# SY_HR08_MCU_INTERFACE_V1_1.net
KiCad netlist of a schematic drawn in Altium Designer
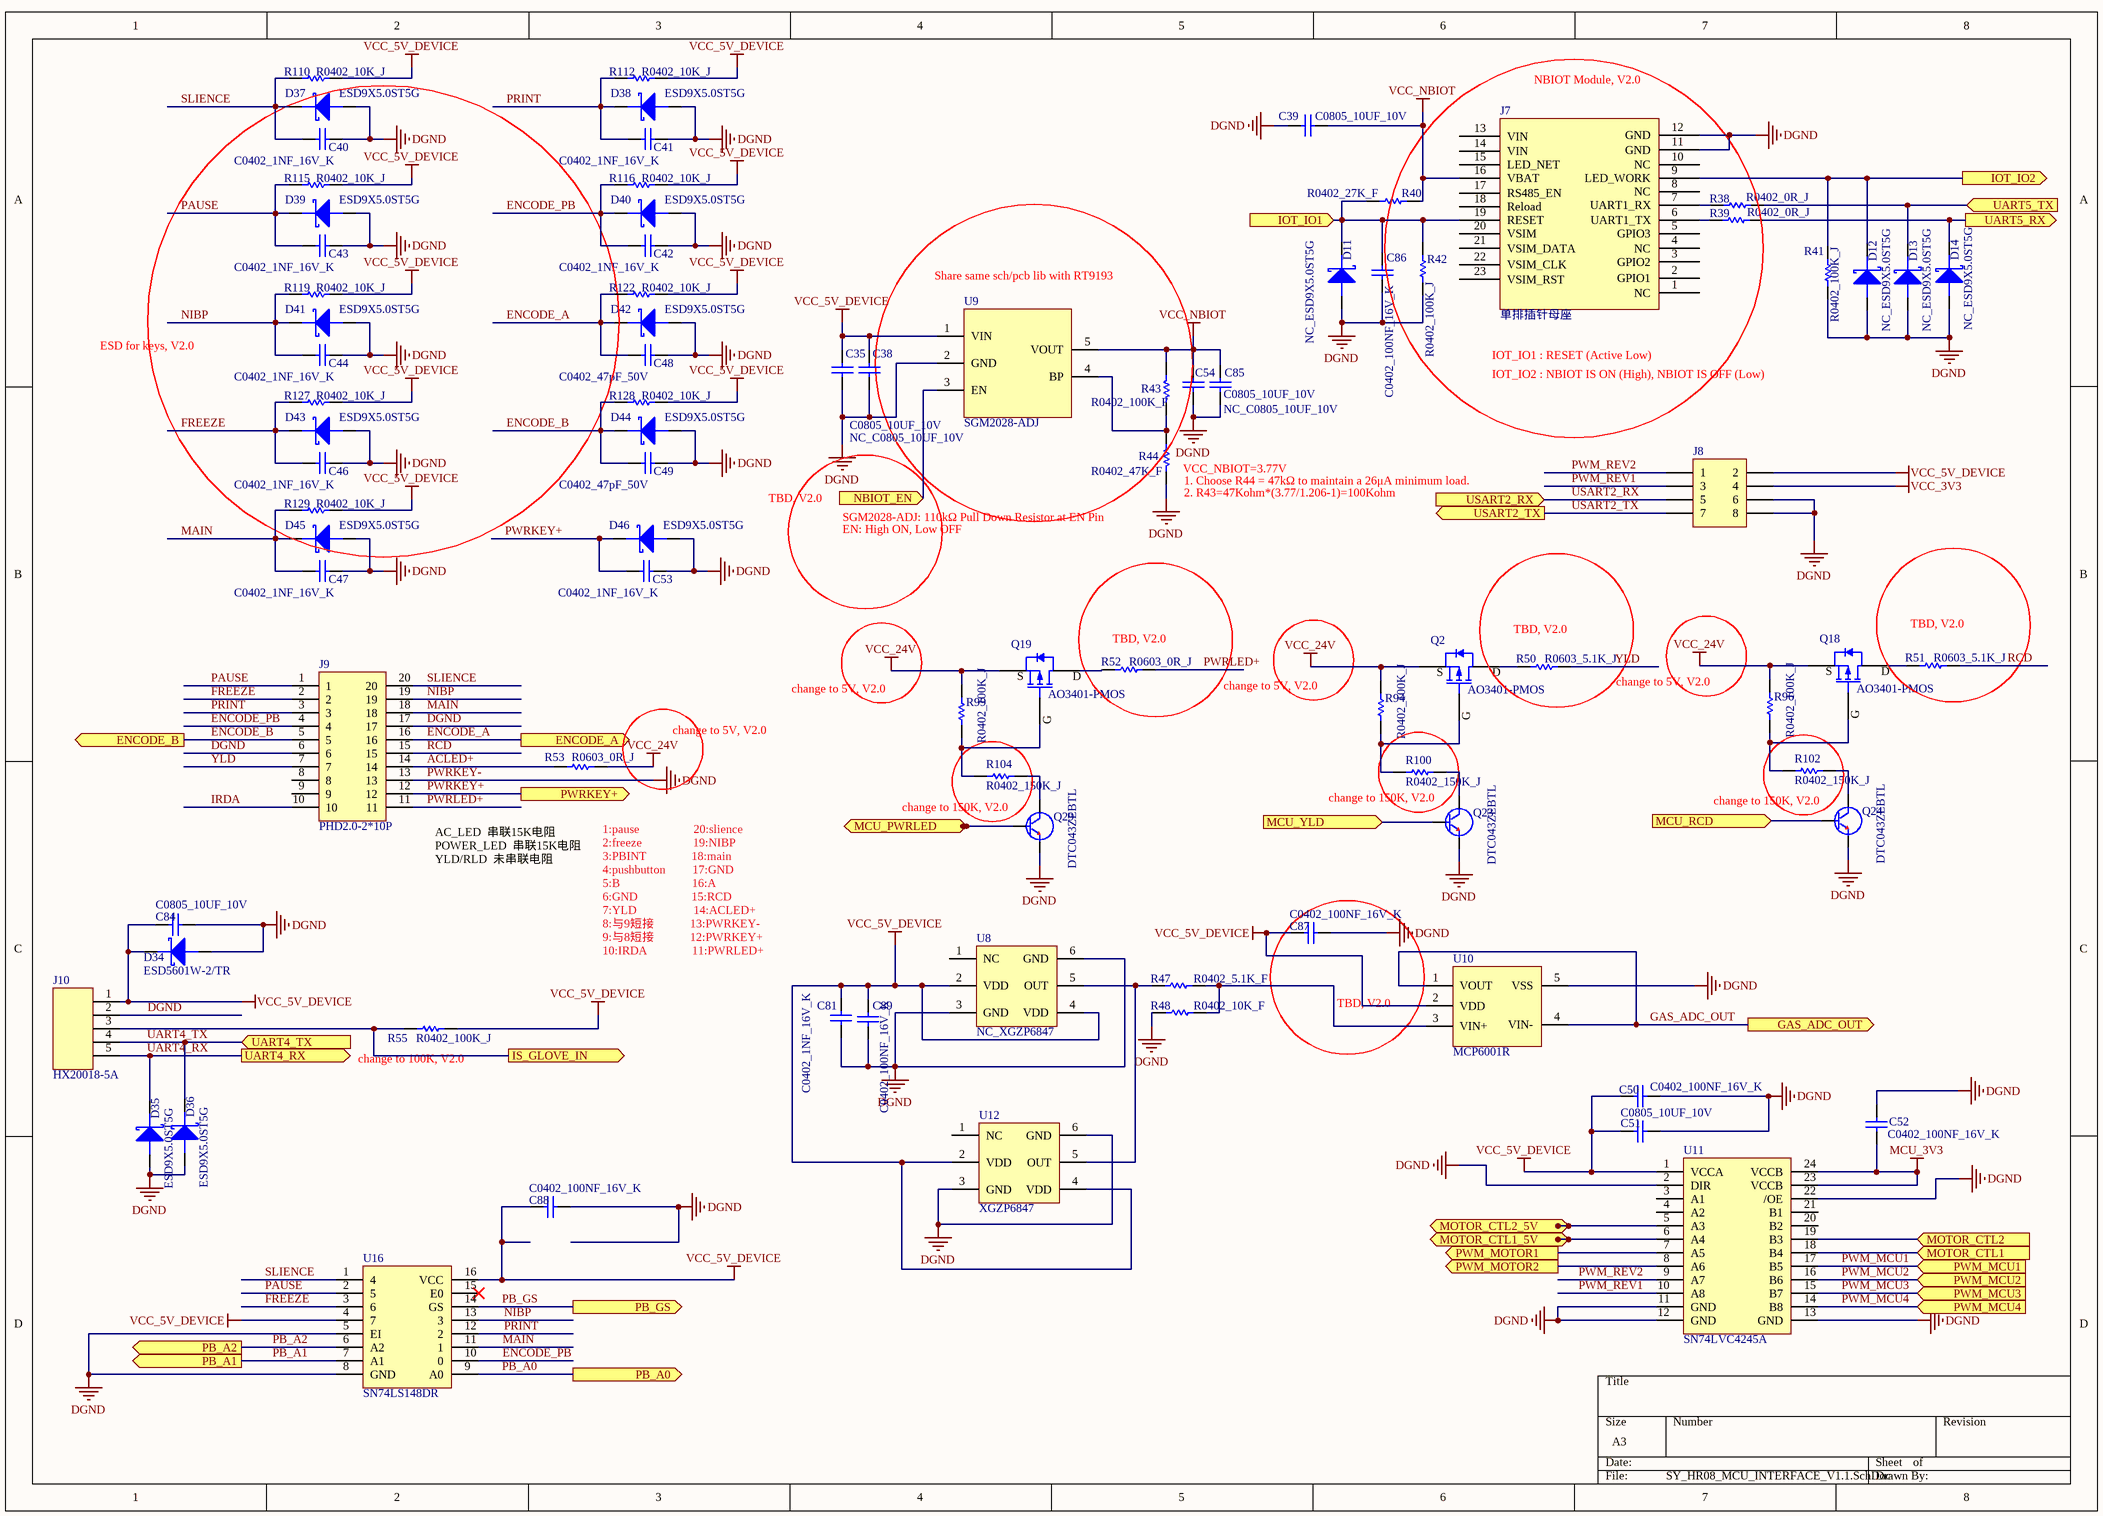
[diagram p0: SY_HR08_MCU_INTERFACE_V1.1.SchDoc]

(export (version "E")
  (design (tool "Eeschema 10.0.6"))
  (components
    (comp (ref "C35")
      (value "C0805_10UF_10V")
      (footprint "CAP0805-B")
      (description "电容_10uF_0805_X5R_10V_K")
      (libsource (lib "zhangky_sch") (part "C0805_10UF_10V"))
    )
    (comp (ref "C38")
      (value "NC_C0805_10UF_10V")
      (footprint "CAP0805-B")
      (description "电容_10uF_0805_X5R_10V_K")
      (libsource (lib "zhangky_sch") (part "C0805_10UF_10V"))
    )
    (comp (ref "C39")
      (value "C0805_10UF_10V")
      (footprint "CAP0805-B")
      (description "电容_10uF_0805_X5R_10V_K")
      (libsource (lib "zhangky_sch") (part "C0805_10UF_10V"))
    )
    (comp (ref "C40")
      (value "C0402_1NF_16V_K")
      (footprint "CAP0402_HQ")
      (description "电容_100nF_0402_X7R_16V_K")
      (libsource (lib "zhangky_sch") (part "C0402_100NF_16V_K"))
    )
    (comp (ref "C41")
      (value "C0402_1NF_16V_K")
      (footprint "CAP0402_HQ")
      (description "电容_100nF_0402_X7R_16V_K")
      (libsource (lib "zhangky_sch") (part "C0402_100NF_16V_K"))
    )
    (comp (ref "C42")
      (value "C0402_1NF_16V_K")
      (footprint "CAP0402_HQ")
      (description "电容_100nF_0402_X7R_16V_K")
      (libsource (lib "zhangky_sch") (part "C0402_100NF_16V_K"))
    )
    (comp (ref "C43")
      (value "C0402_1NF_16V_K")
      (footprint "CAP0402_HQ")
      (description "电容_100nF_0402_X7R_16V_K")
      (libsource (lib "zhangky_sch") (part "C0402_100NF_16V_K"))
    )
    (comp (ref "C44")
      (value "C0402_1NF_16V_K")
      (footprint "CAP0402_HQ")
      (description "电容_100nF_0402_X7R_16V_K")
      (libsource (lib "zhangky_sch") (part "C0402_100NF_16V_K"))
    )
    (comp (ref "C46")
      (value "C0402_1NF_16V_K")
      (footprint "CAP0402_HQ")
      (description "电容_100nF_0402_X7R_16V_K")
      (libsource (lib "zhangky_sch") (part "C0402_100NF_16V_K"))
    )
    (comp (ref "C47")
      (value "C0402_1NF_16V_K")
      (footprint "CAP0402_HQ")
      (description "电容_100nF_0402_X7R_16V_K")
      (libsource (lib "zhangky_sch") (part "C0402_100NF_16V_K"))
    )
    (comp (ref "C48")
      (value "C0402_47pF_50V")
      (footprint "CAP0402_HQ")
      (description "电容_100nF_0402_X7R_16V_K")
      (libsource (lib "zhangky_sch") (part "C0402_100NF_16V_K"))
    )
    (comp (ref "C49")
      (value "C0402_47pF_50V")
      (footprint "CAP0402_HQ")
      (description "电容_100nF_0402_X7R_16V_K")
      (libsource (lib "zhangky_sch") (part "C0402_100NF_16V_K"))
    )
    (comp (ref "C50")
      (value "C0402_100NF_16V_K")
      (footprint "CAP0402_HQ")
      (description "电容_100nF_0402_X7R_16V_K")
      (libsource (lib "zhangky_sch") (part "C0402_100NF_16V_K"))
    )
    (comp (ref "C51")
      (value "C0805_10UF_10V")
      (footprint "CAP0805-B")
      (description "电容_10uF_0805_X5R_10V_K")
      (libsource (lib "zhangky_sch") (part "C0805_10UF_10V"))
    )
    (comp (ref "C52")
      (value "C0402_100NF_16V_K")
      (footprint "CAP0402_HQ")
      (description "电容_100nF_0402_X7R_16V_K")
      (libsource (lib "zhangky_sch") (part "C0402_100NF_16V_K"))
    )
    (comp (ref "C53")
      (value "C0402_1NF_16V_K")
      (footprint "CAP0402_HQ")
      (description "电容_100nF_0402_X7R_16V_K")
      (libsource (lib "zhangky_sch") (part "C0402_100NF_16V_K"))
    )
    (comp (ref "C54")
      (value "NC_C0805_10UF_10V")
      (footprint "CAP0805-B")
      (description "电容_10uF_0805_X5R_10V_K")
      (libsource (lib "zhangky_sch") (part "C0805_10UF_10V"))
    )
    (comp (ref "C81")
      (value "C0402_1NF_16V_K")
      (footprint "CAP0402_HQ")
      (description "电容_100nF_0402_X7R_16V_K")
      (libsource (lib "zhangky_sch") (part "C0402_100NF_16V_K"))
    )
    (comp (ref "C84")
      (value "C0805_10UF_10V")
      (footprint "CAP0805-B")
      (description "电容_10uF_0805_X5R_10V_K")
      (libsource (lib "zhangky_sch") (part "C0805_10UF_10V"))
    )
    (comp (ref "C85")
      (value "C0805_10UF_10V")
      (footprint "CAP0805-B")
      (description "电容_10uF_0805_X5R_10V_K")
      (libsource (lib "zhangky_sch") (part "C0805_10UF_10V"))
    )
    (comp (ref "C86")
      (value "C0402_100NF_16V_K")
      (footprint "CAP0402_HQ")
      (description "电容_100nF_0402_X7R_16V_K")
      (libsource (lib "zhangky_sch") (part "C0402_100NF_16V_K"))
    )
    (comp (ref "C87")
      (value "C0402_100NF_16V_K")
      (footprint "CAP0402_HQ")
      (description "电容_100nF_0402_X7R_16V_K")
      (libsource (lib "zhangky_sch") (part "C0402_100NF_16V_K"))
    )
    (comp (ref "C88")
      (value "C0402_100NF_16V_K")
      (footprint "CAP0402_HQ")
      (description "电容_100nF_0402_X7R_16V_K")
      (libsource (lib "zhangky_sch") (part "C0402_100NF_16V_K"))
    )
    (comp (ref "C89")
      (value "C0402_100NF_16V_K")
      (footprint "CAP0402_HQ")
      (description "电容_100nF_0402_X7R_16V_K")
      (libsource (lib "zhangky_sch") (part "C0402_100NF_16V_K"))
    )
    (comp (ref "D11")
      (value "NC_ESD9X5.0ST5G")
      (footprint "ESD9X5.0ST5G")
      (description "TVS_单路_单向_5.0V_65pF")
      (fields (field (name "MANUFACTURER") "ONSEMI(安森美)") (field (name "PART NUMBER") "HQ11510010010"))
      (libsource (lib "zhangky_sch") (part "ESD9X5.0ST5G"))
    )
    (comp (ref "D12")
      (value "NC_ESD9X5.0ST5G")
      (footprint "ESD9X5.0ST5G")
      (description "TVS_单路_单向_5.0V_65pF")
      (fields (field (name "MANUFACTURER") "ONSEMI(安森美)") (field (name "PART NUMBER") "HQ11510010010"))
      (libsource (lib "zhangky_sch") (part "ESD9X5.0ST5G"))
    )
    (comp (ref "D13")
      (value "NC_ESD9X5.0ST5G")
      (footprint "ESD9X5.0ST5G")
      (description "TVS_单路_单向_5.0V_65pF")
      (fields (field (name "MANUFACTURER") "ONSEMI(安森美)") (field (name "PART NUMBER") "HQ11510010010"))
      (libsource (lib "zhangky_sch") (part "ESD9X5.0ST5G"))
    )
    (comp (ref "D14")
      (value "NC_ESD9X5.0ST5G")
      (footprint "ESD9X5.0ST5G")
      (description "TVS_单路_单向_5.0V_65pF")
      (fields (field (name "MANUFACTURER") "ONSEMI(安森美)") (field (name "PART NUMBER") "HQ11510010010"))
      (libsource (lib "zhangky_sch") (part "ESD9X5.0ST5G"))
    )
    (comp (ref "D34")
      (value "ESD5601W-2/TR")
      (footprint "ESD5601W-2$2F$TR")
      (description "TVS_浪涌+静电二合一管_单向_7V_170pf")
      (fields (field (name "MANUFACTURER") "Will(韦尔)") (field (name "PART NUMBER") "HQ11510029000"))
      (libsource (lib "zhangky_sch") (part "ESD5601W-2/TR"))
    )
    (comp (ref "D35")
      (value "ESD9X5.0ST5G")
      (footprint "ESD9X5.0ST5G")
      (description "TVS_单路_单向_5.0V_65pF")
      (fields (field (name "MANUFACTURER") "ONSEMI(安森美)") (field (name "PART NUMBER") "HQ11510010010"))
      (libsource (lib "zhangky_sch") (part "ESD9X5.0ST5G"))
    )
    (comp (ref "D36")
      (value "ESD9X5.0ST5G")
      (footprint "ESD9X5.0ST5G")
      (description "TVS_单路_单向_5.0V_65pF")
      (fields (field (name "MANUFACTURER") "ONSEMI(安森美)") (field (name "PART NUMBER") "HQ11510010010"))
      (libsource (lib "zhangky_sch") (part "ESD9X5.0ST5G"))
    )
    (comp (ref "D37")
      (value "ESD9X5.0ST5G")
      (footprint "ESD9X5.0ST5G")
      (description "TVS_单路_单向_5.0V_65pF")
      (fields (field (name "MANUFACTURER") "ONSEMI(安森美)") (field (name "PART NUMBER") "HQ11510010010"))
      (libsource (lib "zhangky_sch") (part "ESD9X5.0ST5G"))
    )
    (comp (ref "D38")
      (value "ESD9X5.0ST5G")
      (footprint "ESD9X5.0ST5G")
      (description "TVS_单路_单向_5.0V_65pF")
      (fields (field (name "MANUFACTURER") "ONSEMI(安森美)") (field (name "PART NUMBER") "HQ11510010010"))
      (libsource (lib "zhangky_sch") (part "ESD9X5.0ST5G"))
    )
    (comp (ref "D39")
      (value "ESD9X5.0ST5G")
      (footprint "ESD9X5.0ST5G")
      (description "TVS_单路_单向_5.0V_65pF")
      (fields (field (name "MANUFACTURER") "ONSEMI(安森美)") (field (name "PART NUMBER") "HQ11510010010"))
      (libsource (lib "zhangky_sch") (part "ESD9X5.0ST5G"))
    )
    (comp (ref "D40")
      (value "ESD9X5.0ST5G")
      (footprint "ESD9X5.0ST5G")
      (description "TVS_单路_单向_5.0V_65pF")
      (fields (field (name "MANUFACTURER") "ONSEMI(安森美)") (field (name "PART NUMBER") "HQ11510010010"))
      (libsource (lib "zhangky_sch") (part "ESD9X5.0ST5G"))
    )
    (comp (ref "D41")
      (value "ESD9X5.0ST5G")
      (footprint "ESD9X5.0ST5G")
      (description "TVS_单路_单向_5.0V_65pF")
      (fields (field (name "MANUFACTURER") "ONSEMI(安森美)") (field (name "PART NUMBER") "HQ11510010010"))
      (libsource (lib "zhangky_sch") (part "ESD9X5.0ST5G"))
    )
    (comp (ref "D42")
      (value "ESD9X5.0ST5G")
      (footprint "ESD9X5.0ST5G")
      (description "TVS_单路_单向_5.0V_65pF")
      (fields (field (name "MANUFACTURER") "ONSEMI(安森美)") (field (name "PART NUMBER") "HQ11510010010"))
      (libsource (lib "zhangky_sch") (part "ESD9X5.0ST5G"))
    )
    (comp (ref "D43")
      (value "ESD9X5.0ST5G")
      (footprint "ESD9X5.0ST5G")
      (description "TVS_单路_单向_5.0V_65pF")
      (fields (field (name "MANUFACTURER") "ONSEMI(安森美)") (field (name "PART NUMBER") "HQ11510010010"))
      (libsource (lib "zhangky_sch") (part "ESD9X5.0ST5G"))
    )
    (comp (ref "D44")
      (value "ESD9X5.0ST5G")
      (footprint "ESD9X5.0ST5G")
      (description "TVS_单路_单向_5.0V_65pF")
      (fields (field (name "MANUFACTURER") "ONSEMI(安森美)") (field (name "PART NUMBER") "HQ11510010010"))
      (libsource (lib "zhangky_sch") (part "ESD9X5.0ST5G"))
    )
    (comp (ref "D45")
      (value "ESD9X5.0ST5G")
      (footprint "ESD9X5.0ST5G")
      (description "TVS_单路_单向_5.0V_65pF")
      (fields (field (name "MANUFACTURER") "ONSEMI(安森美)") (field (name "PART NUMBER") "HQ11510010010"))
      (libsource (lib "zhangky_sch") (part "ESD9X5.0ST5G"))
    )
    (comp (ref "D46")
      (value "ESD9X5.0ST5G")
      (footprint "ESD9X5.0ST5G")
      (description "TVS_单路_单向_5.0V_65pF")
      (fields (field (name "MANUFACTURER") "ONSEMI(安森美)") (field (name "PART NUMBER") "HQ11510010010"))
      (libsource (lib "zhangky_sch") (part "ESD9X5.0ST5G"))
    )
    (comp (ref "J7")
      (value "单排插针母座")
      (footprint "USR-LTE-7S4")
      (libsource (lib "USR-NB75 V1.0.1") (part "USR-NB75"))
    )
    (comp (ref "J8")
      (value "双排插针")
      (footprint "CON2X4(2.54MM)")
      (description "Header, 4-Pin, Dual row")
      (libsource (lib "zhangky_sch") (part "Header 4X2"))
    )
    (comp (ref "J9")
      (value "PHD2.0-2*10P")
      (footprint "PHD2.0-20P")
      (description "2.0mm间距接插件 双排插座")
      (libsource (lib "zhangky_sch") (part "PHD2.0-20P"))
    )
    (comp (ref "J10")
      (value "HX20018-5A")
      (footprint "HX20018-5A")
      (description "HX20018-5A  2.0mm")
      (libsource (lib "zhangky_sch") (part "HX20018-5A"))
    )
    (comp (ref "Q2")
      (value "AO3401-PMOS")
      (footprint "AO3400")
      (libsource (lib "zhangky_sch") (part "AO3401-PMOS"))
    )
    (comp (ref "Q18")
      (value "AO3401-PMOS")
      (footprint "AO3400")
      (libsource (lib "zhangky_sch") (part "AO3401-PMOS"))
    )
    (comp (ref "Q19")
      (value "AO3401-PMOS")
      (footprint "AO3400")
      (libsource (lib "zhangky_sch") (part "AO3401-PMOS"))
    )
    (comp (ref "Q23")
      (value "DTC043ZEBTL")
      (footprint "DTC043ZEBTL$2F$$2F$DTC143ZE$2F$$2F$LDTC143ZET1G")
      (description "NPN三极管_100mA_EMT3F")
      (libsource (lib "zhangky_sch") (part "DTC043ZEBTL"))
    )
    (comp (ref "Q24")
      (value "DTC043ZEBTL")
      (footprint "DTC043ZEBTL$2F$$2F$DTC143ZE$2F$$2F$LDTC143ZET1G")
      (description "NPN三极管_100mA_EMT3F")
      (libsource (lib "zhangky_sch") (part "DTC043ZEBTL"))
    )
    (comp (ref "Q29")
      (value "DTC043ZEBTL")
      (footprint "DTC043ZEBTL$2F$$2F$DTC143ZE$2F$$2F$LDTC143ZET1G")
      (description "NPN三极管_100mA_EMT3F")
      (libsource (lib "zhangky_sch") (part "DTC043ZEBTL"))
    )
    (comp (ref "R38")
      (value "R0402_0R_J")
      (footprint "RES0402_HQ")
      (description "电阻10K(0402-0.0625W-J)")
      (libsource (lib "zhangky_sch") (part "R0402_10K_J"))
    )
    (comp (ref "R39")
      (value "R0402_0R_J")
      (footprint "RES0402_HQ")
      (description "电阻10K(0402-0.0625W-J)")
      (libsource (lib "zhangky_sch") (part "R0402_10K_J"))
    )
    (comp (ref "R40")
      (value "R0402_27K_F")
      (footprint "RES0402_HQ")
      (description "电阻10K(0402-0.0625W-J)")
      (libsource (lib "zhangky_sch") (part "R0402_10K_J"))
    )
    (comp (ref "R41")
      (value "R0402_100K_J")
      (footprint "RES0402_HQ")
      (description "电阻10K(0402-0.0625W-J)")
      (libsource (lib "zhangky_sch") (part "R0402_10K_J"))
    )
    (comp (ref "R42")
      (value "R0402_100K_J")
      (footprint "RES0402_HQ")
      (description "电阻10K(0402-0.0625W-J)")
      (libsource (lib "zhangky_sch") (part "R0402_10K_J"))
    )
    (comp (ref "R43")
      (value "R0402_100K_F")
      (footprint "RES0402_HQ")
      (description "电阻10K(0402-0.0625W-J)")
      (libsource (lib "zhangky_sch") (part "R0402_10K_J"))
    )
    (comp (ref "R44")
      (value "R0402_47K_F")
      (footprint "RES0402_HQ")
      (description "电阻10K(0402-0.0625W-J)")
      (libsource (lib "zhangky_sch") (part "R0402_10K_J"))
    )
    (comp (ref "R47")
      (value "R0402_5.1K_F")
      (footprint "RES0402_HQ")
      (description "电阻100K(0402-0.0625W-J)")
      (libsource (lib "zhangky_sch") (part "R0402_100K_J"))
    )
    (comp (ref "R48")
      (value "R0402_10K_F")
      (footprint "RES0402_HQ")
      (description "电阻100K(0402-0.0625W-J)")
      (libsource (lib "zhangky_sch") (part "R0402_100K_J"))
    )
    (comp (ref "R50")
      (value "R0603_5.1K_J")
      (footprint "RES0603-A")
      (description "电阻0R(0603-0.1W-J)")
      (libsource (lib "zhangky_sch") (part "R0603_0R_J"))
    )
    (comp (ref "R51")
      (value "R0603_5.1K_J")
      (footprint "RES0603-A")
      (description "电阻0R(0603-0.1W-J)")
      (libsource (lib "zhangky_sch") (part "R0603_0R_J"))
    )
    (comp (ref "R52")
      (value "R0603_0R_J")
      (footprint "RES0603-A")
      (description "电阻0R(0603-0.1W-J)")
      (libsource (lib "zhangky_sch") (part "R0603_0R_J"))
    )
    (comp (ref "R53")
      (value "R0603_0R_J")
      (footprint "RES0603-A")
      (description "电阻0R(0603-0.1W-J)")
      (libsource (lib "zhangky_sch") (part "R0603_0R_J"))
    )
    (comp (ref "R55")
      (value "R0402_100K_J")
      (footprint "RES0402_HQ")
      (description "电阻10K(0402-0.0625W-J)")
      (libsource (lib "zhangky_sch") (part "R0402_10K_J"))
    )
    (comp (ref "R94")
      (value "R0402_100K_J")
      (footprint "RES0402_HQ")
      (description "电阻100K(0402-0.0625W-J)")
      (libsource (lib "zhangky_sch") (part "R0402_100K_J"))
    )
    (comp (ref "R96")
      (value "R0402_100K_J")
      (footprint "RES0402_HQ")
      (description "电阻100K(0402-0.0625W-J)")
      (libsource (lib "zhangky_sch") (part "R0402_100K_J"))
    )
    (comp (ref "R99")
      (value "R0402_100K_J")
      (footprint "RES0402_HQ")
      (description "电阻100K(0402-0.0625W-J)")
      (libsource (lib "zhangky_sch") (part "R0402_100K_J"))
    )
    (comp (ref "R100")
      (value "R0402_150K_J")
      (footprint "RES0402_HQ")
      (description "电阻100K(0402-0.0625W-J)")
      (libsource (lib "zhangky_sch") (part "R0402_100K_J"))
    )
    (comp (ref "R102")
      (value "R0402_150K_J")
      (footprint "RES0402_HQ")
      (description "电阻100K(0402-0.0625W-J)")
      (libsource (lib "zhangky_sch") (part "R0402_100K_J"))
    )
    (comp (ref "R104")
      (value "R0402_150K_J")
      (footprint "RES0402_HQ")
      (description "电阻100K(0402-0.0625W-J)")
      (libsource (lib "zhangky_sch") (part "R0402_100K_J"))
    )
    (comp (ref "R110")
      (value "R0402_10K_J")
      (footprint "RES0402_HQ")
      (description "电阻10K(0402-0.0625W-J)")
      (libsource (lib "zhangky_sch") (part "R0402_10K_J"))
    )
    (comp (ref "R112")
      (value "R0402_10K_J")
      (footprint "RES0402_HQ")
      (description "电阻10K(0402-0.0625W-J)")
      (libsource (lib "zhangky_sch") (part "R0402_10K_J"))
    )
    (comp (ref "R115")
      (value "R0402_10K_J")
      (footprint "RES0402_HQ")
      (description "电阻10K(0402-0.0625W-J)")
      (libsource (lib "zhangky_sch") (part "R0402_10K_J"))
    )
    (comp (ref "R116")
      (value "R0402_10K_J")
      (footprint "RES0402_HQ")
      (description "电阻10K(0402-0.0625W-J)")
      (libsource (lib "zhangky_sch") (part "R0402_10K_J"))
    )
    (comp (ref "R119")
      (value "R0402_10K_J")
      (footprint "RES0402_HQ")
      (description "电阻10K(0402-0.0625W-J)")
      (libsource (lib "zhangky_sch") (part "R0402_10K_J"))
    )
    (comp (ref "R122")
      (value "R0402_10K_J")
      (footprint "RES0402_HQ")
      (description "电阻10K(0402-0.0625W-J)")
      (libsource (lib "zhangky_sch") (part "R0402_10K_J"))
    )
    (comp (ref "R127")
      (value "R0402_10K_J")
      (footprint "RES0402_HQ")
      (description "电阻10K(0402-0.0625W-J)")
      (libsource (lib "zhangky_sch") (part "R0402_10K_J"))
    )
    (comp (ref "R128")
      (value "R0402_10K_J")
      (footprint "RES0402_HQ")
      (description "电阻10K(0402-0.0625W-J)")
      (libsource (lib "zhangky_sch") (part "R0402_10K_J"))
    )
    (comp (ref "R129")
      (value "R0402_10K_J")
      (footprint "RES0402_HQ")
      (description "电阻10K(0402-0.0625W-J)")
      (libsource (lib "zhangky_sch") (part "R0402_10K_J"))
    )
    (comp (ref "U8")
      (value "NC_XGZP6847")
      (footprint "XGZP6847300KPA")
      (description "XGZP6847_300KPG  气压范围-100kpa - 300kpa")
      (libsource (lib "zhangky_sch") (part "XGZP6847"))
    )
    (comp (ref "U9")
      (value "SGM2028-ADJ")
      (footprint "TPS7B6950")
      (description "单电池电压转换器  3.3V")
      (libsource (lib "zhangky_sch") (part "RT9193-33"))
    )
    (comp (ref "U10")
      (value "MCP6001R")
      (footprint "TOS23")
      (description "1MHz, Low-Power Op Amp")
      (libsource (lib "zhangky_sch") (part "MCP6001R"))
    )
    (comp (ref "U11")
      (value "SN74LVC4245A")
      (footprint "SN74LVC4245APW")
      (description "3.3V 至 5V 移位器")
      (libsource (lib "zhangky_sch") (part "SN74LVC4245AWP"))
    )
    (comp (ref "U12")
      (value "XGZP6847")
      (footprint "XGZP6847300KPA")
      (description "XGZP6847_300KPG  气压范围-100kpa - 300kpa")
      (libsource (lib "zhangky_sch") (part "XGZP6847"))
    )
    (comp (ref "U16")
      (value "SN74LS148DR")
      (footprint "SOIC16_39MM")
      (description "8 线路到 3 线路优先编码器")
      (libsource (lib "zhangky_sch") (part "SN74LS148DR"))
    )
  )
  (nets
    (net (code "1") (name "/ACLED+") (class "Default")
      (node (ref "J9") (pin "14") (pinfunction "14_14") (pintype "passive"))
      (node (ref "R53") (pin "1") (pinfunction "1_1") (pintype "passive"))
    )
    (net (code "2") (name "/ENCODE_A") (class "Default")
      (node (ref "C48") (pin "2") (pinfunction "2_2") (pintype "passive"))
      (node (ref "D42") (pin "1") (pinfunction "1_1") (pintype "passive"))
      (node (ref "J9") (pin "16") (pinfunction "16_16") (pintype "passive"))
      (node (ref "R122") (pin "1") (pinfunction "1_1") (pintype "passive"))
    )
    (net (code "3") (name "/ENCODE_B") (class "Default")
      (node (ref "C49") (pin "2") (pinfunction "2_2") (pintype "passive"))
      (node (ref "D44") (pin "1") (pinfunction "1_1") (pintype "passive"))
      (node (ref "J9") (pin "5") (pinfunction "5_5") (pintype "passive"))
      (node (ref "R128") (pin "1") (pinfunction "1_1") (pintype "passive"))
    )
    (net (code "4") (name "/ENCODE_PB") (class "Default")
      (node (ref "C42") (pin "2") (pinfunction "2_2") (pintype "passive"))
      (node (ref "D40") (pin "1") (pinfunction "1_1") (pintype "passive"))
      (node (ref "J9") (pin "4") (pinfunction "4_4") (pintype "passive"))
      (node (ref "R116") (pin "1") (pinfunction "1_1") (pintype "passive"))
      (node (ref "U16") (pin "10") (pinfunction "0_10") (pintype "passive"))
    )
    (net (code "5") (name "/FREEZE") (class "Default")
      (node (ref "C46") (pin "2") (pinfunction "2_2") (pintype "passive"))
      (node (ref "D43") (pin "1") (pinfunction "1_1") (pintype "passive"))
      (node (ref "J9") (pin "2") (pinfunction "2_2") (pintype "passive"))
      (node (ref "R127") (pin "1") (pinfunction "1_1") (pintype "passive"))
      (node (ref "U16") (pin "3") (pinfunction "6_3") (pintype "passive"))
    )
    (net (code "6") (name "/GAS_ADC_OUT") (class "Default")
      (node (ref "U10") (pin "1") (pinfunction "VOUT_1") (pintype "passive"))
      (node (ref "U10") (pin "4") (pinfunction "VIN-_4") (pintype "passive"))
    )
    (net (code "7") (name "/IOT_IO1") (class "Default")
      (node (ref "C86") (pin "1") (pinfunction "1_1") (pintype "passive"))
      (node (ref "D11") (pin "1") (pinfunction "1_1") (pintype "passive"))
      (node (ref "J7") (pin "19") (pinfunction "RESET_19") (pintype "passive"))
      (node (ref "R40") (pin "2") (pinfunction "2_2") (pintype "passive"))
      (node (ref "R42") (pin "1") (pinfunction "1_1") (pintype "passive"))
    )
    (net (code "8") (name "/IOT_IO2") (class "Default")
      (node (ref "D12") (pin "1") (pinfunction "1_1") (pintype "passive"))
      (node (ref "J7") (pin "9") (pinfunction "LED_WORK_9") (pintype "passive"))
      (node (ref "R41") (pin "2") (pinfunction "2_2") (pintype "passive"))
    )
    (net (code "9") (name "/IRDA") (class "Default")
      (node (ref "J9") (pin "10") (pinfunction "10_10") (pintype "passive"))
    )
    (net (code "10") (name "/IS_GLOVE_IN") (class "Default")
      (node (ref "J10") (pin "3") (pinfunction "3_3") (pintype "passive"))
      (node (ref "R55") (pin "1") (pinfunction "1_1") (pintype "passive"))
    )
    (net (code "11") (name "/MAIN") (class "Default")
      (node (ref "C47") (pin "2") (pinfunction "2_2") (pintype "passive"))
      (node (ref "D45") (pin "1") (pinfunction "1_1") (pintype "passive"))
      (node (ref "J9") (pin "18") (pinfunction "18_18") (pintype "passive"))
      (node (ref "R129") (pin "1") (pinfunction "1_1") (pintype "passive"))
      (node (ref "U16") (pin "11") (pinfunction "1_11") (pintype "passive"))
    )
    (net (code "12") (name "/MCU_PWRLED") (class "Default")
      (node (ref "Q29") (pin "1") (pinfunction "B_1") (pintype "passive"))
    )
    (net (code "13") (name "/MCU_RCD") (class "Default")
      (node (ref "Q24") (pin "1") (pinfunction "B_1") (pintype "passive"))
    )
    (net (code "14") (name "/MCU_YLD") (class "Default")
      (node (ref "Q23") (pin "1") (pinfunction "B_1") (pintype "passive"))
    )
    (net (code "15") (name "/MOTOR_CTL1") (class "Default")
      (node (ref "U11") (pin "18") (pinfunction "B4_18") (pintype "passive"))
    )
    (net (code "16") (name "/MOTOR_CTL1_5V") (class "Default")
      (node (ref "U11") (pin "6") (pinfunction "A4_6") (pintype "passive"))
    )
    (net (code "17") (name "/MOTOR_CTL2") (class "Default")
      (node (ref "U11") (pin "19") (pinfunction "B3_19") (pintype "passive"))
    )
    (net (code "18") (name "/MOTOR_CTL2_5V") (class "Default")
      (node (ref "U11") (pin "5") (pinfunction "A3_5") (pintype "passive"))
    )
    (net (code "19") (name "/NBIOT_EN") (class "Default")
      (node (ref "U9") (pin "3") (pinfunction "EN_3") (pintype "passive"))
    )
    (net (code "20") (name "/NIBP") (class "Default")
      (node (ref "C44") (pin "2") (pinfunction "2_2") (pintype "passive"))
      (node (ref "D41") (pin "1") (pinfunction "1_1") (pintype "passive"))
      (node (ref "J9") (pin "19") (pinfunction "19_19") (pintype "passive"))
      (node (ref "R119") (pin "1") (pinfunction "1_1") (pintype "passive"))
      (node (ref "U16") (pin "13") (pinfunction "3_13") (pintype "passive"))
    )
    (net (code "21") (name "/PAUSE") (class "Default")
      (node (ref "C43") (pin "2") (pinfunction "2_2") (pintype "passive"))
      (node (ref "D39") (pin "1") (pinfunction "1_1") (pintype "passive"))
      (node (ref "J9") (pin "1") (pinfunction "1_1") (pintype "passive"))
      (node (ref "R115") (pin "1") (pinfunction "1_1") (pintype "passive"))
      (node (ref "U16") (pin "2") (pinfunction "5_2") (pintype "passive"))
    )
    (net (code "22") (name "/PB_A0") (class "Default")
      (node (ref "U16") (pin "9") (pinfunction "A0_9") (pintype "passive"))
    )
    (net (code "23") (name "/PB_A1") (class "Default")
      (node (ref "U16") (pin "7") (pinfunction "A1_7") (pintype "passive"))
    )
    (net (code "24") (name "/PB_A2") (class "Default")
      (node (ref "U16") (pin "6") (pinfunction "A2_6") (pintype "passive"))
    )
    (net (code "25") (name "/PB_GS") (class "Default")
      (node (ref "U16") (pin "14") (pinfunction "GS_14") (pintype "passive"))
    )
    (net (code "26") (name "/PRINT") (class "Default")
      (node (ref "C41") (pin "2") (pinfunction "2_2") (pintype "passive"))
      (node (ref "D38") (pin "1") (pinfunction "1_1") (pintype "passive"))
      (node (ref "J9") (pin "3") (pinfunction "3_3") (pintype "passive"))
      (node (ref "R112") (pin "1") (pinfunction "1_1") (pintype "passive"))
      (node (ref "U16") (pin "12") (pinfunction "2_12") (pintype "passive"))
    )
    (net (code "27") (name "/PWM_MCU1") (class "Default")
      (node (ref "U11") (pin "17") (pinfunction "B5_17") (pintype "passive"))
    )
    (net (code "28") (name "/PWM_MCU2") (class "Default")
      (node (ref "U11") (pin "16") (pinfunction "B6_16") (pintype "passive"))
    )
    (net (code "29") (name "/PWM_MCU3") (class "Default")
      (node (ref "U11") (pin "15") (pinfunction "B7_15") (pintype "passive"))
    )
    (net (code "30") (name "/PWM_MCU4") (class "Default")
      (node (ref "U11") (pin "14") (pinfunction "B8_14") (pintype "passive"))
    )
    (net (code "31") (name "/PWM_MOTOR1") (class "Default")
      (node (ref "U11") (pin "7") (pinfunction "A5_7") (pintype "passive"))
    )
    (net (code "32") (name "/PWM_MOTOR2") (class "Default")
      (node (ref "U11") (pin "8") (pinfunction "A6_8") (pintype "passive"))
    )
    (net (code "33") (name "/PWM_REV1") (class "Default")
      (node (ref "J8") (pin "3") (pinfunction "3_3") (pintype "passive"))
      (node (ref "U11") (pin "10") (pinfunction "A8_10") (pintype "passive"))
    )
    (net (code "34") (name "/PWM_REV2") (class "Default")
      (node (ref "J8") (pin "1") (pinfunction "1_1") (pintype "passive"))
      (node (ref "U11") (pin "9") (pinfunction "A7_9") (pintype "passive"))
    )
    (net (code "35") (name "/PWRKEY+") (class "Default")
      (node (ref "C53") (pin "2") (pinfunction "2_2") (pintype "passive"))
      (node (ref "D46") (pin "1") (pinfunction "1_1") (pintype "passive"))
      (node (ref "J9") (pin "12") (pinfunction "12_12") (pintype "passive"))
    )
    (net (code "36") (name "/PWRLED+") (class "Default")
      (node (ref "J9") (pin "11") (pinfunction "11_11") (pintype "passive"))
      (node (ref "R52") (pin "2") (pinfunction "2_2") (pintype "passive"))
    )
    (net (code "37") (name "/RCD") (class "Default")
      (node (ref "J9") (pin "15") (pinfunction "15_15") (pintype "passive"))
      (node (ref "R51") (pin "2") (pinfunction "2_2") (pintype "passive"))
    )
    (net (code "38") (name "/SLIENCE") (class "Default")
      (node (ref "C40") (pin "2") (pinfunction "2_2") (pintype "passive"))
      (node (ref "D37") (pin "1") (pinfunction "1_1") (pintype "passive"))
      (node (ref "J9") (pin "20") (pinfunction "20_20") (pintype "passive"))
      (node (ref "R110") (pin "1") (pinfunction "1_1") (pintype "passive"))
      (node (ref "U16") (pin "1") (pinfunction "4_1") (pintype "passive"))
    )
    (net (code "39") (name "/UART4_RX") (class "Default")
      (node (ref "D35") (pin "1") (pinfunction "1_1") (pintype "passive"))
      (node (ref "J10") (pin "5") (pinfunction "5_5") (pintype "passive"))
    )
    (net (code "40") (name "/UART4_TX") (class "Default")
      (node (ref "D36") (pin "1") (pinfunction "1_1") (pintype "passive"))
      (node (ref "J10") (pin "4") (pinfunction "4_4") (pintype "passive"))
    )
    (net (code "41") (name "/UART5_RX") (class "Default")
      (node (ref "D14") (pin "1") (pinfunction "1_1") (pintype "passive"))
      (node (ref "R39") (pin "1") (pinfunction "1_1") (pintype "passive"))
    )
    (net (code "42") (name "/UART5_TX") (class "Default")
      (node (ref "D13") (pin "1") (pinfunction "1_1") (pintype "passive"))
      (node (ref "R38") (pin "2") (pinfunction "2_2") (pintype "passive"))
    )
    (net (code "43") (name "/USART2_RX") (class "Default")
      (node (ref "J8") (pin "5") (pinfunction "5_5") (pintype "passive"))
    )
    (net (code "44") (name "/USART2_TX") (class "Default")
      (node (ref "J8") (pin "7") (pinfunction "7_7") (pintype "passive"))
    )
    (net (code "45") (name "/YLD") (class "Default")
      (node (ref "J9") (pin "7") (pinfunction "7_7") (pintype "passive"))
      (node (ref "R50") (pin "2") (pinfunction "2_2") (pintype "passive"))
    )
    (net (code "46") (name "DGND") (class "Default")
      (node (ref "C35") (pin "1") (pinfunction "1_1") (pintype "passive"))
      (node (ref "C38") (pin "1") (pinfunction "1_1") (pintype "passive"))
      (node (ref "C39") (pin "2") (pinfunction "2_2") (pintype "passive"))
      (node (ref "C40") (pin "1") (pinfunction "1_1") (pintype "passive"))
      (node (ref "C41") (pin "1") (pinfunction "1_1") (pintype "passive"))
      (node (ref "C42") (pin "1") (pinfunction "1_1") (pintype "passive"))
      (node (ref "C43") (pin "1") (pinfunction "1_1") (pintype "passive"))
      (node (ref "C44") (pin "1") (pinfunction "1_1") (pintype "passive"))
      (node (ref "C46") (pin "1") (pinfunction "1_1") (pintype "passive"))
      (node (ref "C47") (pin "1") (pinfunction "1_1") (pintype "passive"))
      (node (ref "C48") (pin "1") (pinfunction "1_1") (pintype "passive"))
      (node (ref "C49") (pin "1") (pinfunction "1_1") (pintype "passive"))
      (node (ref "C50") (pin "1") (pinfunction "1_1") (pintype "passive"))
      (node (ref "C51") (pin "2") (pinfunction "2_2") (pintype "passive"))
      (node (ref "C52") (pin "1") (pinfunction "1_1") (pintype "passive"))
      (node (ref "C53") (pin "1") (pinfunction "1_1") (pintype "passive"))
      (node (ref "C54") (pin "1") (pinfunction "1_1") (pintype "passive"))
      (node (ref "C81") (pin "2") (pinfunction "2_2") (pintype "passive"))
      (node (ref "C84") (pin "2") (pinfunction "2_2") (pintype "passive"))
      (node (ref "C85") (pin "1") (pinfunction "1_1") (pintype "passive"))
      (node (ref "C86") (pin "2") (pinfunction "2_2") (pintype "passive"))
      (node (ref "C87") (pin "1") (pinfunction "1_1") (pintype "passive"))
      (node (ref "C88") (pin "1") (pinfunction "1_1") (pintype "passive"))
      (node (ref "C89") (pin "2") (pinfunction "2_2") (pintype "passive"))
      (node (ref "D11") (pin "2") (pinfunction "2_2") (pintype "passive"))
      (node (ref "D12") (pin "2") (pinfunction "2_2") (pintype "passive"))
      (node (ref "D13") (pin "2") (pinfunction "2_2") (pintype "passive"))
      (node (ref "D14") (pin "2") (pinfunction "2_2") (pintype "passive"))
      (node (ref "D34") (pin "2") (pinfunction "2_2") (pintype "passive"))
      (node (ref "D35") (pin "2") (pinfunction "2_2") (pintype "passive"))
      (node (ref "D36") (pin "2") (pinfunction "2_2") (pintype "passive"))
      (node (ref "D37") (pin "2") (pinfunction "2_2") (pintype "passive"))
      (node (ref "D38") (pin "2") (pinfunction "2_2") (pintype "passive"))
      (node (ref "D39") (pin "2") (pinfunction "2_2") (pintype "passive"))
      (node (ref "D40") (pin "2") (pinfunction "2_2") (pintype "passive"))
      (node (ref "D41") (pin "2") (pinfunction "2_2") (pintype "passive"))
      (node (ref "D42") (pin "2") (pinfunction "2_2") (pintype "passive"))
      (node (ref "D43") (pin "2") (pinfunction "2_2") (pintype "passive"))
      (node (ref "D44") (pin "2") (pinfunction "2_2") (pintype "passive"))
      (node (ref "D45") (pin "2") (pinfunction "2_2") (pintype "passive"))
      (node (ref "D46") (pin "2") (pinfunction "2_2") (pintype "passive"))
      (node (ref "J10") (pin "2") (pinfunction "2_2") (pintype "passive"))
      (node (ref "J7") (pin "11") (pinfunction "GND_11") (pintype "passive"))
      (node (ref "J7") (pin "12") (pinfunction "GND_12") (pintype "passive"))
      (node (ref "J8") (pin "6") (pinfunction "6_6") (pintype "passive"))
      (node (ref "J8") (pin "8") (pinfunction "8_8") (pintype "passive"))
      (node (ref "J9") (pin "13") (pinfunction "13_13") (pintype "passive"))
      (node (ref "J9") (pin "17") (pinfunction "17_17") (pintype "passive"))
      (node (ref "J9") (pin "6") (pinfunction "6_6") (pintype "passive"))
      (node (ref "Q23") (pin "2") (pinfunction "E_2") (pintype "passive"))
      (node (ref "Q24") (pin "2") (pinfunction "E_2") (pintype "passive"))
      (node (ref "Q29") (pin "2") (pinfunction "E_2") (pintype "passive"))
      (node (ref "R41") (pin "1") (pinfunction "1_1") (pintype "passive"))
      (node (ref "R42") (pin "2") (pinfunction "2_2") (pintype "passive"))
      (node (ref "R44") (pin "1") (pinfunction "1_1") (pintype "passive"))
      (node (ref "R48") (pin "2") (pinfunction "2_2") (pintype "passive"))
      (node (ref "U10") (pin "5") (pinfunction "VSS_5") (pintype "passive"))
      (node (ref "U11") (pin "11") (pinfunction "GND_11") (pintype "passive"))
      (node (ref "U11") (pin "12") (pinfunction "GND_12") (pintype "passive"))
      (node (ref "U11") (pin "13") (pinfunction "GND_13") (pintype "passive"))
      (node (ref "U11") (pin "2") (pinfunction "DIR_2") (pintype "passive"))
      (node (ref "U11") (pin "22") (pinfunction "/OE_22") (pintype "passive"))
      (node (ref "U12") (pin "3") (pinfunction "GND_3") (pintype "passive"))
      (node (ref "U12") (pin "6") (pinfunction "GND_6") (pintype "passive"))
      (node (ref "U16") (pin "5") (pinfunction "EI_5") (pintype "passive"))
      (node (ref "U16") (pin "8") (pinfunction "GND_8") (pintype "passive"))
      (node (ref "U8") (pin "3") (pinfunction "GND_3") (pintype "passive"))
      (node (ref "U8") (pin "6") (pinfunction "GND_6") (pintype "passive"))
      (node (ref "U9") (pin "2") (pinfunction "GND_2") (pintype "passive"))
    )
    (net (code "47") (name "MCU_3V3") (class "Default")
      (node (ref "C52") (pin "2") (pinfunction "2_2") (pintype "passive"))
      (node (ref "U11") (pin "23") (pinfunction "VCCB_23") (pintype "passive"))
      (node (ref "U11") (pin "24") (pinfunction "VCCB_24") (pintype "passive"))
    )
    (net (code "48") (name "Net-(J7-UART1_RX)") (class "Default")
      (node (ref "J7") (pin "7") (pinfunction "UART1_RX_7") (pintype "passive"))
      (node (ref "R38") (pin "1") (pinfunction "1_1") (pintype "passive"))
    )
    (net (code "49") (name "Net-(J7-UART1_TX)") (class "Default")
      (node (ref "J7") (pin "6") (pinfunction "UART1_TX_6") (pintype "passive"))
      (node (ref "R39") (pin "2") (pinfunction "2_2") (pintype "passive"))
    )
    (net (code "50") (name "Net-(Q2-D)") (class "Default")
      (node (ref "Q2") (pin "3") (pinfunction "D_3") (pintype "passive"))
      (node (ref "R50") (pin "1") (pinfunction "1_1") (pintype "passive"))
    )
    (net (code "51") (name "Net-(Q2-G)") (class "Default")
      (node (ref "Q2") (pin "1") (pinfunction "G_1") (pintype "passive"))
      (node (ref "R100") (pin "2") (pinfunction "2_2") (pintype "passive"))
      (node (ref "R94") (pin "1") (pinfunction "1_1") (pintype "passive"))
    )
    (net (code "52") (name "Net-(Q18-D)") (class "Default")
      (node (ref "Q18") (pin "3") (pinfunction "D_3") (pintype "passive"))
      (node (ref "R51") (pin "1") (pinfunction "1_1") (pintype "passive"))
    )
    (net (code "53") (name "Net-(Q18-G)") (class "Default")
      (node (ref "Q18") (pin "1") (pinfunction "G_1") (pintype "passive"))
      (node (ref "R102") (pin "2") (pinfunction "2_2") (pintype "passive"))
      (node (ref "R96") (pin "1") (pinfunction "1_1") (pintype "passive"))
    )
    (net (code "54") (name "Net-(Q19-D)") (class "Default")
      (node (ref "Q19") (pin "3") (pinfunction "D_3") (pintype "passive"))
      (node (ref "R52") (pin "1") (pinfunction "1_1") (pintype "passive"))
    )
    (net (code "55") (name "Net-(Q19-G)") (class "Default")
      (node (ref "Q19") (pin "1") (pinfunction "G_1") (pintype "passive"))
      (node (ref "R104") (pin "2") (pinfunction "2_2") (pintype "passive"))
      (node (ref "R99") (pin "1") (pinfunction "1_1") (pintype "passive"))
    )
    (net (code "56") (name "Net-(Q23-C)") (class "Default")
      (node (ref "Q23") (pin "3") (pinfunction "C_3") (pintype "passive"))
      (node (ref "R100") (pin "1") (pinfunction "1_1") (pintype "passive"))
    )
    (net (code "57") (name "Net-(Q24-C)") (class "Default")
      (node (ref "Q24") (pin "3") (pinfunction "C_3") (pintype "passive"))
      (node (ref "R102") (pin "1") (pinfunction "1_1") (pintype "passive"))
    )
    (net (code "58") (name "Net-(Q29-C)") (class "Default")
      (node (ref "Q29") (pin "3") (pinfunction "C_3") (pintype "passive"))
      (node (ref "R104") (pin "1") (pinfunction "1_1") (pintype "passive"))
    )
    (net (code "59") (name "Net-(U9-BP)") (class "Default")
      (node (ref "R43") (pin "1") (pinfunction "1_1") (pintype "passive"))
      (node (ref "R44") (pin "2") (pinfunction "2_2") (pintype "passive"))
      (node (ref "U9") (pin "4") (pinfunction "BP_4") (pintype "passive"))
    )
    (net (code "60") (name "Net-(U10-VIN+)") (class "Default")
      (node (ref "R47") (pin "1") (pinfunction "1_1") (pintype "passive"))
      (node (ref "R48") (pin "1") (pinfunction "1_1") (pintype "passive"))
      (node (ref "U10") (pin "3") (pinfunction "VIN+_3") (pintype "passive"))
    )
    (net (code "61") (name "Net-(U12-OUT)") (class "Default")
      (node (ref "R47") (pin "2") (pinfunction "2_2") (pintype "passive"))
      (node (ref "U12") (pin "5") (pinfunction "OUT_5") (pintype "passive"))
      (node (ref "U8") (pin "5") (pinfunction "OUT_5") (pintype "passive"))
    )
    (net (code "62") (name "VCC_3V3") (class "Default")
      (node (ref "J8") (pin "4") (pinfunction "4_4") (pintype "passive"))
    )
    (net (code "63") (name "VCC_5V_DEVICE") (class "Default")
      (node (ref "C35") (pin "2") (pinfunction "2_2") (pintype "passive"))
      (node (ref "C38") (pin "2") (pinfunction "2_2") (pintype "passive"))
      (node (ref "C50") (pin "2") (pinfunction "2_2") (pintype "passive"))
      (node (ref "C51") (pin "1") (pinfunction "1_1") (pintype "passive"))
      (node (ref "C81") (pin "1") (pinfunction "1_1") (pintype "passive"))
      (node (ref "C84") (pin "1") (pinfunction "1_1") (pintype "passive"))
      (node (ref "C87") (pin "2") (pinfunction "2_2") (pintype "passive"))
      (node (ref "C88") (pin "2") (pinfunction "2_2") (pintype "passive"))
      (node (ref "C89") (pin "1") (pinfunction "1_1") (pintype "passive"))
      (node (ref "D34") (pin "1") (pinfunction "1_1") (pintype "passive"))
      (node (ref "J10") (pin "1") (pinfunction "1_1") (pintype "passive"))
      (node (ref "J8") (pin "2") (pinfunction "2_2") (pintype "passive"))
      (node (ref "R110") (pin "2") (pinfunction "2_2") (pintype "passive"))
      (node (ref "R112") (pin "2") (pinfunction "2_2") (pintype "passive"))
      (node (ref "R115") (pin "2") (pinfunction "2_2") (pintype "passive"))
      (node (ref "R116") (pin "2") (pinfunction "2_2") (pintype "passive"))
      (node (ref "R119") (pin "2") (pinfunction "2_2") (pintype "passive"))
      (node (ref "R122") (pin "2") (pinfunction "2_2") (pintype "passive"))
      (node (ref "R127") (pin "2") (pinfunction "2_2") (pintype "passive"))
      (node (ref "R128") (pin "2") (pinfunction "2_2") (pintype "passive"))
      (node (ref "R129") (pin "2") (pinfunction "2_2") (pintype "passive"))
      (node (ref "R55") (pin "2") (pinfunction "2_2") (pintype "passive"))
      (node (ref "U10") (pin "2") (pinfunction "VDD_2") (pintype "passive"))
      (node (ref "U11") (pin "1") (pinfunction "VCCA_1") (pintype "passive"))
      (node (ref "U12") (pin "2") (pinfunction "VDD_2") (pintype "passive"))
      (node (ref "U12") (pin "4") (pinfunction "VDD_4") (pintype "passive"))
      (node (ref "U16") (pin "16") (pinfunction "VCC_16") (pintype "passive"))
      (node (ref "U16") (pin "4") (pinfunction "7_4") (pintype "passive"))
      (node (ref "U8") (pin "2") (pinfunction "VDD_2") (pintype "passive"))
      (node (ref "U8") (pin "4") (pinfunction "VDD_4") (pintype "passive"))
      (node (ref "U9") (pin "1") (pinfunction "VIN_1") (pintype "passive"))
    )
    (net (code "64") (name "VCC_24V") (class "Default")
      (node (ref "Q18") (pin "2") (pinfunction "S_2") (pintype "passive"))
      (node (ref "Q19") (pin "2") (pinfunction "S_2") (pintype "passive"))
      (node (ref "Q2") (pin "2") (pinfunction "S_2") (pintype "passive"))
      (node (ref "R53") (pin "2") (pinfunction "2_2") (pintype "passive"))
      (node (ref "R94") (pin "2") (pinfunction "2_2") (pintype "passive"))
      (node (ref "R96") (pin "2") (pinfunction "2_2") (pintype "passive"))
      (node (ref "R99") (pin "2") (pinfunction "2_2") (pintype "passive"))
    )
    (net (code "65") (name "VCC_NBIOT") (class "Default")
      (node (ref "C39") (pin "1") (pinfunction "1_1") (pintype "passive"))
      (node (ref "C54") (pin "2") (pinfunction "2_2") (pintype "passive"))
      (node (ref "C85") (pin "2") (pinfunction "2_2") (pintype "passive"))
      (node (ref "J7") (pin "16") (pinfunction "VBAT_16") (pintype "passive"))
      (node (ref "R40") (pin "1") (pinfunction "1_1") (pintype "passive"))
      (node (ref "R43") (pin "2") (pinfunction "2_2") (pintype "passive"))
      (node (ref "U9") (pin "5") (pinfunction "VOUT_5") (pintype "passive"))
    )
    (net (code "66") (name "unconnected-(J7-GPIO1-Pad2)") (class "Default")
      (node (ref "J7") (pin "2") (pinfunction "GPIO1_2") (pintype "passive"))
    )
    (net (code "67") (name "unconnected-(J7-GPIO2-Pad3)") (class "Default")
      (node (ref "J7") (pin "3") (pinfunction "GPIO2_3") (pintype "passive"))
    )
    (net (code "68") (name "unconnected-(J7-GPIO3-Pad5)") (class "Default")
      (node (ref "J7") (pin "5") (pinfunction "GPIO3_5") (pintype "passive"))
    )
    (net (code "69") (name "unconnected-(J7-LED_NET-Pad15)") (class "Default")
      (node (ref "J7") (pin "15") (pinfunction "LED_NET_15") (pintype "passive"))
    )
    (net (code "70") (name "unconnected-(J7-NC-Pad1)") (class "Default")
      (node (ref "J7") (pin "1") (pinfunction "NC_1") (pintype "passive"))
    )
    (net (code "71") (name "unconnected-(J7-NC-Pad4)") (class "Default")
      (node (ref "J7") (pin "4") (pinfunction "NC_4") (pintype "passive"))
    )
    (net (code "72") (name "unconnected-(J7-NC-Pad8)") (class "Default")
      (node (ref "J7") (pin "8") (pinfunction "NC_8") (pintype "passive"))
    )
    (net (code "73") (name "unconnected-(J7-NC-Pad10)") (class "Default")
      (node (ref "J7") (pin "10") (pinfunction "NC_10") (pintype "passive"))
    )
    (net (code "74") (name "unconnected-(J7-RS485_EN-Pad17)") (class "Default")
      (node (ref "J7") (pin "17") (pinfunction "RS485_EN_17") (pintype "passive"))
    )
    (net (code "75") (name "unconnected-(J7-Reload-Pad18)") (class "Default")
      (node (ref "J7") (pin "18") (pinfunction "Reload_18") (pintype "passive"))
    )
    (net (code "76") (name "unconnected-(J7-VIN-Pad13)") (class "Default")
      (node (ref "J7") (pin "13") (pinfunction "VIN_13") (pintype "passive"))
    )
    (net (code "77") (name "unconnected-(J7-VIN-Pad14)") (class "Default")
      (node (ref "J7") (pin "14") (pinfunction "VIN_14") (pintype "passive"))
    )
    (net (code "78") (name "unconnected-(J7-VSIM-Pad20)") (class "Default")
      (node (ref "J7") (pin "20") (pinfunction "VSIM_20") (pintype "passive"))
    )
    (net (code "79") (name "unconnected-(J7-VSIM_CLK-Pad22)") (class "Default")
      (node (ref "J7") (pin "22") (pinfunction "VSIM_CLK_22") (pintype "passive"))
    )
    (net (code "80") (name "unconnected-(J7-VSIM_DATA-Pad21)") (class "Default")
      (node (ref "J7") (pin "21") (pinfunction "VSIM_DATA_21") (pintype "passive"))
    )
    (net (code "81") (name "unconnected-(J7-VSIM_RST-Pad23)") (class "Default")
      (node (ref "J7") (pin "23") (pinfunction "VSIM_RST_23") (pintype "passive"))
    )
    (net (code "82") (name "unconnected-(J9-Pad8)") (class "Default")
      (node (ref "J9") (pin "8") (pinfunction "8_8") (pintype "passive"))
    )
    (net (code "83") (name "unconnected-(J9-Pad9)") (class "Default")
      (node (ref "J9") (pin "9") (pinfunction "9_9") (pintype "passive"))
    )
    (net (code "84") (name "unconnected-(U8-NC-Pad1)") (class "Default")
      (node (ref "U8") (pin "1") (pinfunction "NC_1") (pintype "passive"))
    )
    (net (code "85") (name "unconnected-(U11-A1-Pad3)") (class "Default")
      (node (ref "U11") (pin "3") (pinfunction "A1_3") (pintype "passive"))
    )
    (net (code "86") (name "unconnected-(U11-A2-Pad4)") (class "Default")
      (node (ref "U11") (pin "4") (pinfunction "A2_4") (pintype "passive"))
    )
    (net (code "87") (name "unconnected-(U11-B1-Pad21)") (class "Default")
      (node (ref "U11") (pin "21") (pinfunction "B1_21") (pintype "passive"))
    )
    (net (code "88") (name "unconnected-(U11-B2-Pad20)") (class "Default")
      (node (ref "U11") (pin "20") (pinfunction "B2_20") (pintype "passive"))
    )
    (net (code "89") (name "unconnected-(U12-NC-Pad1)") (class "Default")
      (node (ref "U12") (pin "1") (pinfunction "NC_1") (pintype "passive"))
    )
    (net (code "90") (name "unconnected-(U16-E0-Pad15)") (class "Default")
      (node (ref "U16") (pin "15") (pinfunction "E0_15") (pintype "passive+no_connect"))
    )
  )
)
